# dBreathe.net
KiCad netlist of a schematic drawn in EAGLE
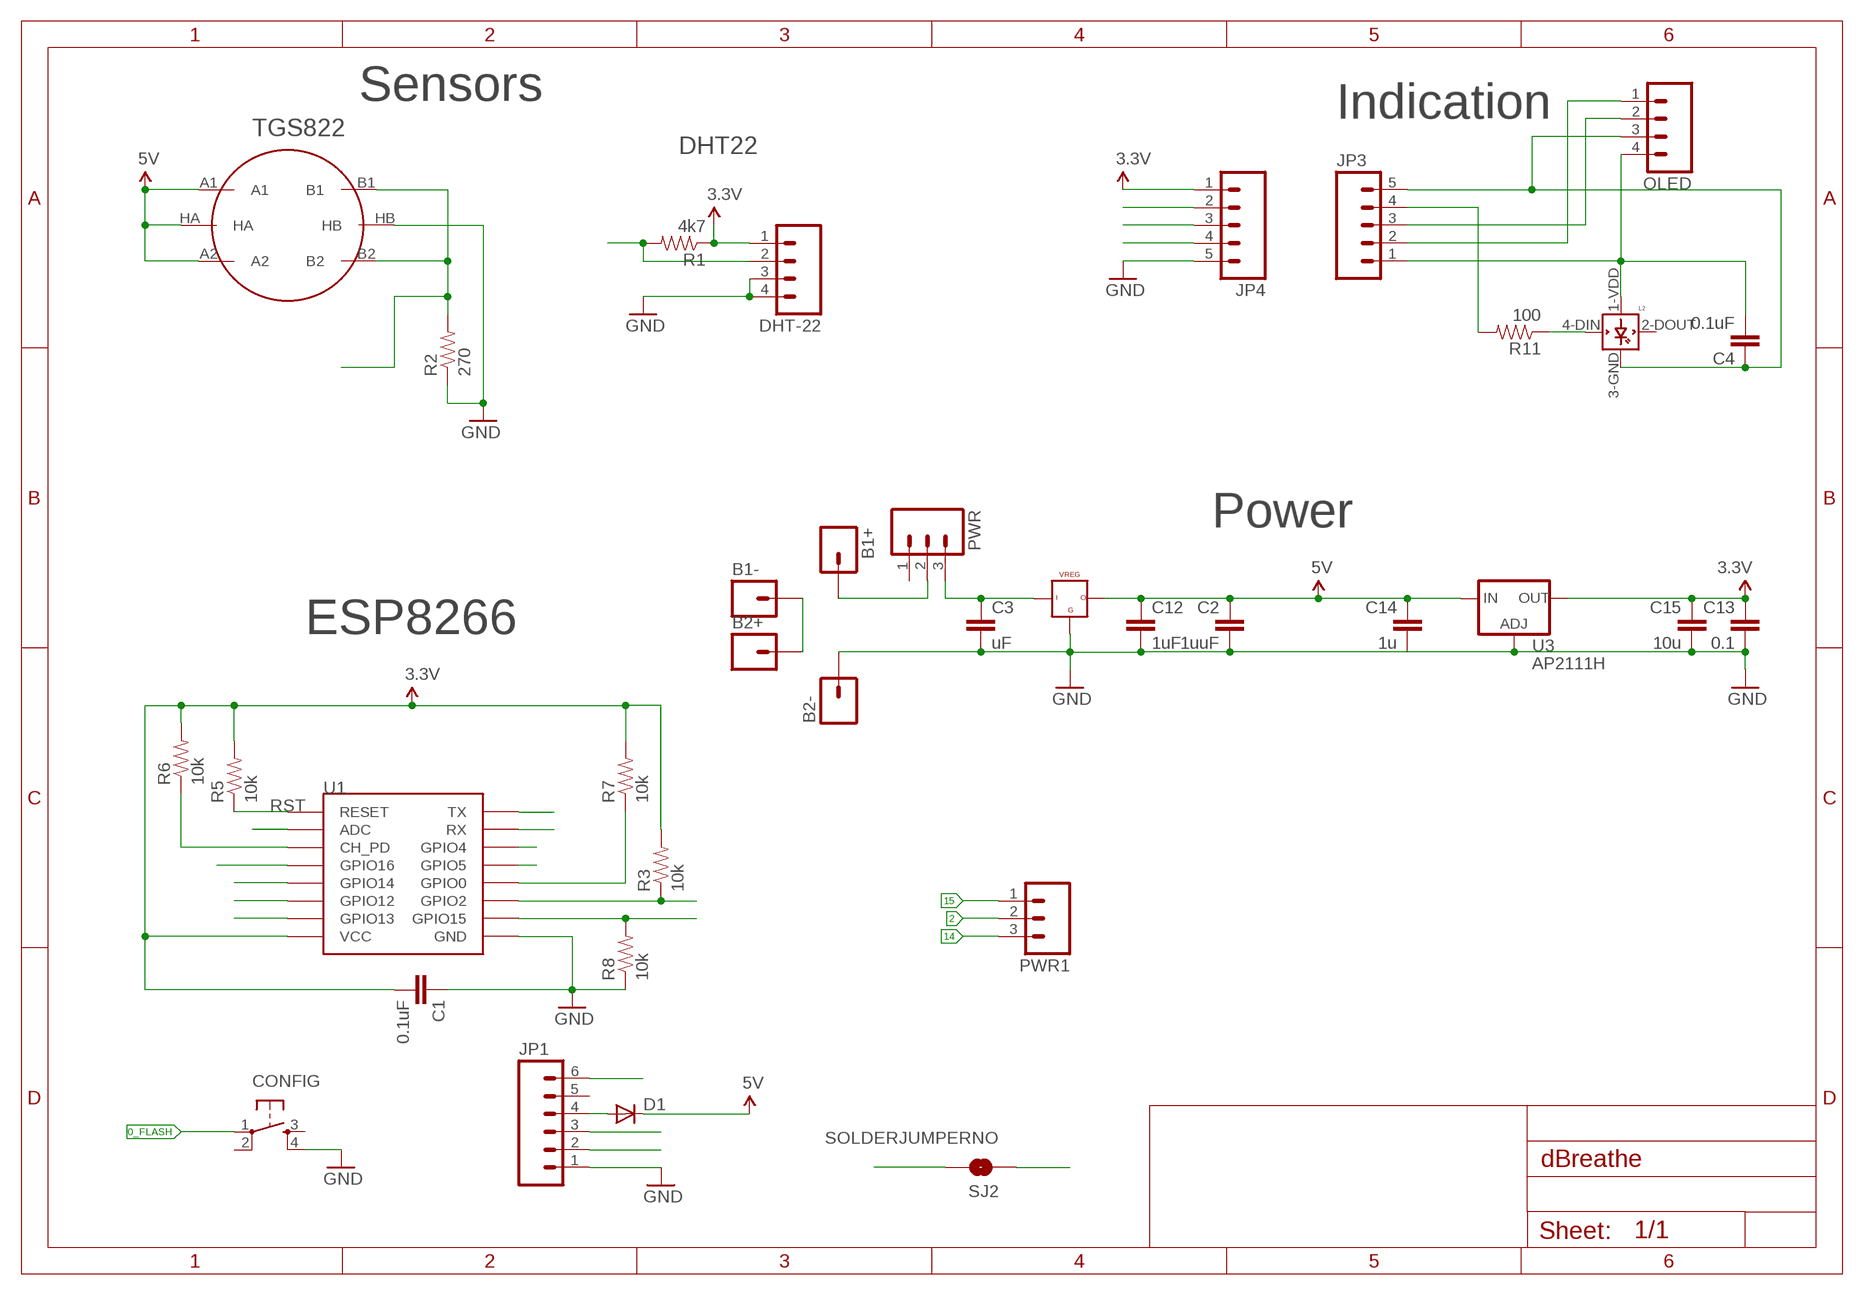
[diagram p0: schematic, sheet 1]

(export (version "E")
  (design (tool "Eeschema 10.0.6"))
  (components
    (comp (ref "B1+")
      (value "M01PTH")
      (footprint "eagle-import:1X01")
      (libsource (lib "eagle-import") (part "M01PTH"))
    )
    (comp (ref "B1-")
      (value "M01PTH")
      (footprint "eagle-import:1X01")
      (libsource (lib "eagle-import") (part "M01PTH"))
    )
    (comp (ref "B2+")
      (value "M01PTH")
      (footprint "eagle-import:1X01")
      (libsource (lib "eagle-import") (part "M01PTH"))
    )
    (comp (ref "B2-")
      (value "M01PTH")
      (footprint "eagle-import:1X01")
      (libsource (lib "eagle-import") (part "M01PTH"))
    )
    (comp (ref "C1")
      (value "0.1uF")
      (footprint "eagle-import:0805")
      (libsource (lib "eagle-import") (part "SparkFun-Capacitors_CAP0805"))
    )
    (comp (ref "C2")
      (value "1uuF")
      (footprint "eagle-import:0805")
      (libsource (lib "eagle-import") (part "CAP0805"))
    )
    (comp (ref "C3")
      (value "uF")
      (footprint "eagle-import:0805")
      (libsource (lib "eagle-import") (part "SparkFun-Capacitors_CAP0805"))
    )
    (comp (ref "C4")
      (value "0.1uF")
      (footprint "eagle-import:0805")
      (libsource (lib "eagle-import") (part "SparkFun-Capacitors_CAP0805"))
    )
    (comp (ref "C12")
      (value "1uF")
      (footprint "eagle-import:0805")
      (libsource (lib "eagle-import") (part "SparkFun-Capacitors_CAP0805"))
    )
    (comp (ref "C13")
      (value "0.1")
      (footprint "eagle-import:0805")
      (libsource (lib "eagle-import") (part "CAP0805"))
    )
    (comp (ref "C14")
      (value "1u")
      (footprint "eagle-import:0805")
      (libsource (lib "eagle-import") (part "CAP0805"))
    )
    (comp (ref "C15")
      (value "10u")
      (footprint "eagle-import:0805-CAP")
      (libsource (lib "eagle-import") (part "CAP0805-CAP"))
    )
    (comp (ref "CONFIG")
      (value "TAC_SWITCHSMD")
      (footprint "eagle-import:TACTILE_SWITCH_SMD")
      (libsource (lib "eagle-import") (part "TAC_SWITCHSMD"))
    )
    (comp (ref "D1")
      (value "DIODESOD")
      (footprint "eagle-import:SOD-323")
      (libsource (lib "eagle-import") (part "DIODESOD"))
    )
    (comp (ref "DHT-22")
      (value "M04PTH")
      (footprint "eagle-import:1X04")
      (libsource (lib "eagle-import") (part "M04PTH"))
    )
    (comp (ref "JP1")
      (value "M06NO_SILK_FEMALE_PTH")
      (footprint "eagle-import:1X06_NO_SILK")
      (libsource (lib "eagle-import") (part "M06NO_SILK_FEMALE_PTH"))
    )
    (comp (ref "JP3")
      (value "M05PTH")
      (footprint "eagle-import:1X05")
      (libsource (lib "eagle-import") (part "M05PTH"))
    )
    (comp (ref "JP4")
      (value "M05PTH")
      (footprint "eagle-import:1X05")
      (libsource (lib "eagle-import") (part "M05PTH"))
    )
    (comp (ref "L2")
      (value "WS2812B")
      (footprint "eagle-import:WS2812B")
      (libsource (lib "eagle-import") (part "WS2812B"))
    )
    (comp (ref "OLED")
      (value "M041X04_NO_SILK")
      (footprint "eagle-import:1X04_NO_SILK")
      (libsource (lib "eagle-import") (part "M041X04_NO_SILK"))
    )
    (comp (ref "PWR")
      (value "M03PTH")
      (footprint "eagle-import:1X03")
      (libsource (lib "eagle-import") (part "M03PTH"))
    )
    (comp (ref "PWR1")
      (value "M03PTH")
      (footprint "eagle-import:1X03")
      (libsource (lib "eagle-import") (part "M03PTH"))
    )
    (comp (ref "R1")
      (value "4k7")
      (footprint "eagle-import:0805")
      (libsource (lib "eagle-import") (part "SparkFun-Resistors_RESISTOR0805-RES"))
    )
    (comp (ref "R2")
      (value "270")
      (footprint "eagle-import:0805")
      (libsource (lib "eagle-import") (part "RESISTOR0805"))
    )
    (comp (ref "R3")
      (value "10k")
      (footprint "eagle-import:0805")
      (libsource (lib "eagle-import") (part "RESISTOR0805"))
    )
    (comp (ref "R5")
      (value "10k")
      (footprint "eagle-import:0805")
      (libsource (lib "eagle-import") (part "RESISTOR0805"))
    )
    (comp (ref "R6")
      (value "10k")
      (footprint "eagle-import:0805")
      (libsource (lib "eagle-import") (part "RESISTOR0805"))
    )
    (comp (ref "R7")
      (value "10k")
      (footprint "eagle-import:0805")
      (libsource (lib "eagle-import") (part "RESISTOR0805"))
    )
    (comp (ref "R8")
      (value "10k")
      (footprint "eagle-import:0805")
      (libsource (lib "eagle-import") (part "RESISTOR0805"))
    )
    (comp (ref "R11")
      (value "100")
      (footprint "eagle-import:0805")
      (libsource (lib "eagle-import") (part "RESISTOR0805"))
    )
    (comp (ref "SJ2")
      (value "SOLDERJUMPERNO")
      (footprint "eagle-import:SJ_2S-NO")
      (libsource (lib "eagle-import") (part "SOLDERJUMPERNO"))
    )
    (comp (ref "U$4")
      (value "VREG_5V")
      (footprint "eagle-import:DPACK")
      (libsource (lib "eagle-import") (part "VREG_5V"))
    )
    (comp (ref "U$7")
      (value "METHANE_SENSOR")
      (footprint "eagle-import:MQ-3")
      (libsource (lib "eagle-import") (part "METHANE_SENSOR"))
    )
    (comp (ref "U1")
      (value "ESP12SMD")
      (footprint "eagle-import:ESP12-SMD")
      (libsource (lib "eagle-import") (part "ESP12SMD"))
    )
    (comp (ref "U3")
      (value "AP2111H")
      (footprint "eagle-import:SOT223")
      (libsource (lib "eagle-import") (part "V_REG_317SMD"))
    )
  )
  (nets
    (net (code "1") (name "0_FLASH") (class "Default")
      (node (ref "CONFIG") (pin "1") (pinfunction "1_1") (pintype "passive"))
      (node (ref "JP1") (pin "6") (pinfunction "6_6") (pintype "passive"))
      (node (ref "R7") (pin "1") (pinfunction "1_1") (pintype "passive"))
      (node (ref "U1") (pin "GPIO0") (pinfunction "GPIO0_GPIO0") (pintype "bidirectional"))
    )
    (net (code "2") (name "2") (class "Default")
      (node (ref "PWR1") (pin "2") (pinfunction "2_2") (pintype "passive"))
      (node (ref "R3") (pin "1") (pinfunction "1_1") (pintype "passive"))
      (node (ref "U1") (pin "GPIO2") (pinfunction "GPIO2_GPIO2") (pintype "bidirectional"))
    )
    (net (code "3") (name "3.3V") (class "Default")
      (node (ref "C1") (pin "2") (pinfunction "2_2") (pintype "passive"))
      (node (ref "C13") (pin "1") (pinfunction "1_1") (pintype "passive"))
      (node (ref "C15") (pin "1") (pinfunction "1_1") (pintype "passive"))
      (node (ref "DHT-22") (pin "1") (pinfunction "1_1") (pintype "passive"))
      (node (ref "JP4") (pin "1") (pinfunction "1_1") (pintype "passive"))
      (node (ref "R1") (pin "1") (pinfunction "1_1") (pintype "passive"))
      (node (ref "R3") (pin "2") (pinfunction "2_2") (pintype "passive"))
      (node (ref "R5") (pin "2") (pinfunction "2_2") (pintype "passive"))
      (node (ref "R6") (pin "2") (pinfunction "2_2") (pintype "passive"))
      (node (ref "R7") (pin "2") (pinfunction "2_2") (pintype "passive"))
      (node (ref "U1") (pin "VCC") (pinfunction "VCC_VCC") (pintype "bidirectional"))
      (node (ref "U3") (pin "2") (pinfunction "OUT_2") (pintype "output"))
    )
    (net (code "4") (name "4_SDA") (class "Default")
      (node (ref "JP4") (pin "2") (pinfunction "2_2") (pintype "passive"))
      (node (ref "U1") (pin "GPIO5") (pinfunction "GPIO5_GPIO5") (pintype "bidirectional"))
    )
    (net (code "5") (name "5V") (class "Default")
      (node (ref "C12") (pin "1") (pinfunction "1_1") (pintype "passive"))
      (node (ref "C14") (pin "1") (pinfunction "1_1") (pintype "passive"))
      (node (ref "C2") (pin "1") (pinfunction "1_1") (pintype "passive"))
      (node (ref "D1") (pin "1") (pinfunction "C_1") (pintype "passive"))
      (node (ref "U$4") (pin "3") (pinfunction "3_3") (pintype "bidirectional"))
      (node (ref "U$7") (pin "A1") (pinfunction "A1_A1") (pintype "bidirectional"))
      (node (ref "U$7") (pin "A2") (pinfunction "A2_A2") (pintype "bidirectional"))
      (node (ref "U$7") (pin "HA") (pinfunction "HA_HA") (pintype "bidirectional"))
      (node (ref "U3") (pin "3") (pinfunction "IN_3") (pintype "input"))
    )
    (net (code "6") (name "5_SCL") (class "Default")
      (node (ref "JP4") (pin "3") (pinfunction "3_3") (pintype "passive"))
      (node (ref "U1") (pin "GPIO4") (pinfunction "GPIO4_GPIO4") (pintype "bidirectional"))
    )
    (net (code "7") (name "12_WS2812") (class "Default")
      (node (ref "JP4") (pin "4") (pinfunction "4_4") (pintype "passive"))
      (node (ref "U1") (pin "GPIO12") (pinfunction "GPIO12_GPIO12") (pintype "bidirectional"))
    )
    (net (code "8") (name "13_DHT") (class "Default")
      (node (ref "DHT-22") (pin "2") (pinfunction "2_2") (pintype "passive"))
      (node (ref "R1") (pin "2") (pinfunction "2_2") (pintype "passive"))
      (node (ref "U1") (pin "GPIO13") (pinfunction "GPIO13_GPIO13") (pintype "bidirectional"))
    )
    (net (code "9") (name "14") (class "Default")
      (node (ref "PWR1") (pin "3") (pinfunction "3_3") (pintype "passive"))
      (node (ref "U1") (pin "GPIO14") (pinfunction "GPIO14_GPIO14") (pintype "bidirectional"))
    )
    (net (code "10") (name "15") (class "Default")
      (node (ref "PWR1") (pin "1") (pinfunction "1_1") (pintype "passive"))
      (node (ref "R8") (pin "2") (pinfunction "2_2") (pintype "passive"))
      (node (ref "U1") (pin "GPIO15") (pinfunction "GPIO15_GPIO15") (pintype "bidirectional"))
    )
    (net (code "11") (name "16_DSLEEP") (class "Default")
      (node (ref "SJ2") (pin "2") (pinfunction "2_2") (pintype "passive"))
      (node (ref "U1") (pin "GPIO16") (pinfunction "GPIO16_GPIO16") (pintype "bidirectional"))
    )
    (net (code "12") (name "ADC") (class "Default")
      (node (ref "R2") (pin "2") (pinfunction "2_2") (pintype "passive"))
      (node (ref "U$7") (pin "B1") (pinfunction "B1_B1") (pintype "bidirectional"))
      (node (ref "U$7") (pin "B2") (pinfunction "B2_B2") (pintype "bidirectional"))
      (node (ref "U1") (pin "ADC") (pinfunction "ADC_ADC") (pintype "bidirectional"))
    )
    (net (code "13") (name "GND") (class "Default")
      (node (ref "B2-") (pin "1") (pinfunction "1_1") (pintype "passive"))
      (node (ref "C1") (pin "1") (pinfunction "1_1") (pintype "passive"))
      (node (ref "C12") (pin "2") (pinfunction "2_2") (pintype "passive"))
      (node (ref "C13") (pin "2") (pinfunction "2_2") (pintype "passive"))
      (node (ref "C14") (pin "2") (pinfunction "2_2") (pintype "passive"))
      (node (ref "C15") (pin "2") (pinfunction "2_2") (pintype "passive"))
      (node (ref "C2") (pin "2") (pinfunction "2_2") (pintype "passive"))
      (node (ref "C3") (pin "2") (pinfunction "2_2") (pintype "passive"))
      (node (ref "CONFIG") (pin "4") (pinfunction "4_4") (pintype "passive"))
      (node (ref "DHT-22") (pin "3") (pinfunction "3_3") (pintype "passive"))
      (node (ref "DHT-22") (pin "4") (pinfunction "4_4") (pintype "passive"))
      (node (ref "JP1") (pin "1") (pinfunction "1_1") (pintype "passive"))
      (node (ref "JP4") (pin "5") (pinfunction "5_5") (pintype "passive"))
      (node (ref "R2") (pin "1") (pinfunction "1_1") (pintype "passive"))
      (node (ref "R8") (pin "1") (pinfunction "1_1") (pintype "passive"))
      (node (ref "U$4") (pin "2") (pinfunction "2_2") (pintype "bidirectional"))
      (node (ref "U$7") (pin "HB") (pinfunction "HB_HB") (pintype "bidirectional"))
      (node (ref "U1") (pin "GND") (pinfunction "GND_GND") (pintype "bidirectional"))
      (node (ref "U3") (pin "1") (pinfunction "ADJ_1") (pintype "input"))
    )
    (net (code "14") (name "Net-(B1+-Pad1)") (class "Default")
      (node (ref "B1+") (pin "1") (pinfunction "1_1") (pintype "passive"))
      (node (ref "PWR") (pin "2") (pinfunction "2_2") (pintype "passive"))
    )
    (net (code "15") (name "Net-(B1--Pad1)") (class "Default")
      (node (ref "B1-") (pin "1") (pinfunction "1_1") (pintype "passive"))
      (node (ref "B2+") (pin "1") (pinfunction "1_1") (pintype "passive"))
    )
    (net (code "16") (name "Net-(C3-Pad1)") (class "Default")
      (node (ref "C3") (pin "1") (pinfunction "1_1") (pintype "passive"))
      (node (ref "PWR") (pin "3") (pinfunction "3_3") (pintype "passive"))
      (node (ref "U$4") (pin "1") (pinfunction "1_1") (pintype "bidirectional"))
    )
    (net (code "17") (name "Net-(D1-A)") (class "Default")
      (node (ref "D1") (pin "2") (pinfunction "A_2") (pintype "passive"))
      (node (ref "JP1") (pin "4") (pinfunction "4_4") (pintype "passive"))
    )
    (net (code "18") (name "Net-(JP3-Pad2)") (class "Default")
      (node (ref "JP3") (pin "2") (pinfunction "2_2") (pintype "passive"))
      (node (ref "OLED") (pin "1") (pinfunction "1_1") (pintype "passive"))
    )
    (net (code "19") (name "Net-(JP3-Pad3)") (class "Default")
      (node (ref "JP3") (pin "3") (pinfunction "3_3") (pintype "passive"))
      (node (ref "OLED") (pin "2") (pinfunction "2_2") (pintype "passive"))
    )
    (net (code "20") (name "Net-(JP3-Pad4)") (class "Default")
      (node (ref "JP3") (pin "4") (pinfunction "4_4") (pintype "passive"))
      (node (ref "R11") (pin "2") (pinfunction "2_2") (pintype "passive"))
    )
    (net (code "21") (name "Net-(L2-DIN)") (class "Default")
      (node (ref "L2") (pin "4-DIN") (pinfunction "DIN_4-DIN") (pintype "input"))
      (node (ref "R11") (pin "1") (pinfunction "1_1") (pintype "passive"))
    )
    (net (code "22") (name "Net-(L2-GND)") (class "Default")
      (node (ref "C4") (pin "1") (pinfunction "1_1") (pintype "passive"))
      (node (ref "JP3") (pin "5") (pinfunction "5_5") (pintype "passive"))
      (node (ref "L2") (pin "3-GND") (pinfunction "GND_3-GND") (pintype "bidirectional"))
      (node (ref "OLED") (pin "3") (pinfunction "3_3") (pintype "passive"))
    )
    (net (code "23") (name "Net-(L2-VDD)") (class "Default")
      (node (ref "C4") (pin "2") (pinfunction "2_2") (pintype "passive"))
      (node (ref "JP3") (pin "1") (pinfunction "1_1") (pintype "passive"))
      (node (ref "L2") (pin "1-VDD") (pinfunction "VDD_1-VDD") (pintype "bidirectional"))
      (node (ref "OLED") (pin "4") (pinfunction "4_4") (pintype "passive"))
    )
    (net (code "24") (name "Net-(R6-Pad1)") (class "Default")
      (node (ref "R6") (pin "1") (pinfunction "1_1") (pintype "passive"))
      (node (ref "U1") (pin "CH_PD") (pinfunction "CH_PD_CH_PD") (pintype "bidirectional"))
    )
    (net (code "25") (name "RST") (class "Default")
      (node (ref "R5") (pin "1") (pinfunction "1_1") (pintype "passive"))
      (node (ref "SJ2") (pin "1") (pinfunction "1_1") (pintype "passive"))
      (node (ref "U1") (pin "RESET") (pinfunction "RESET_RESET") (pintype "bidirectional"))
    )
    (net (code "26") (name "RX") (class "Default")
      (node (ref "JP1") (pin "2") (pinfunction "2_2") (pintype "passive"))
      (node (ref "U1") (pin "TXD0") (pinfunction "TX_TXD0") (pintype "bidirectional"))
    )
    (net (code "27") (name "TX") (class "Default")
      (node (ref "JP1") (pin "3") (pinfunction "3_3") (pintype "passive"))
      (node (ref "U1") (pin "RXD0") (pinfunction "RX_RXD0") (pintype "bidirectional"))
    )
    (net (code "28") (name "unconnected-(CONFIG-Pad2)") (class "Default")
      (node (ref "CONFIG") (pin "2") (pinfunction "2_2") (pintype "passive"))
    )
    (net (code "29") (name "unconnected-(CONFIG-Pad3)") (class "Default")
      (node (ref "CONFIG") (pin "3") (pinfunction "3_3") (pintype "passive"))
    )
    (net (code "30") (name "unconnected-(JP1-Pad5)") (class "Default")
      (node (ref "JP1") (pin "5") (pinfunction "5_5") (pintype "passive"))
    )
    (net (code "31") (name "unconnected-(L2-DOUT-Pad2-DOUT)") (class "Default")
      (node (ref "L2") (pin "2-DOUT") (pinfunction "DOUT_2-DOUT") (pintype "output"))
    )
    (net (code "32") (name "unconnected-(PWR-Pad1)") (class "Default")
      (node (ref "PWR") (pin "1") (pinfunction "1_1") (pintype "passive"))
    )
  )
)
